# vacuumboard_eurobot2014_r1.net
KiCad netlist of a schematic drawn in EAGLE
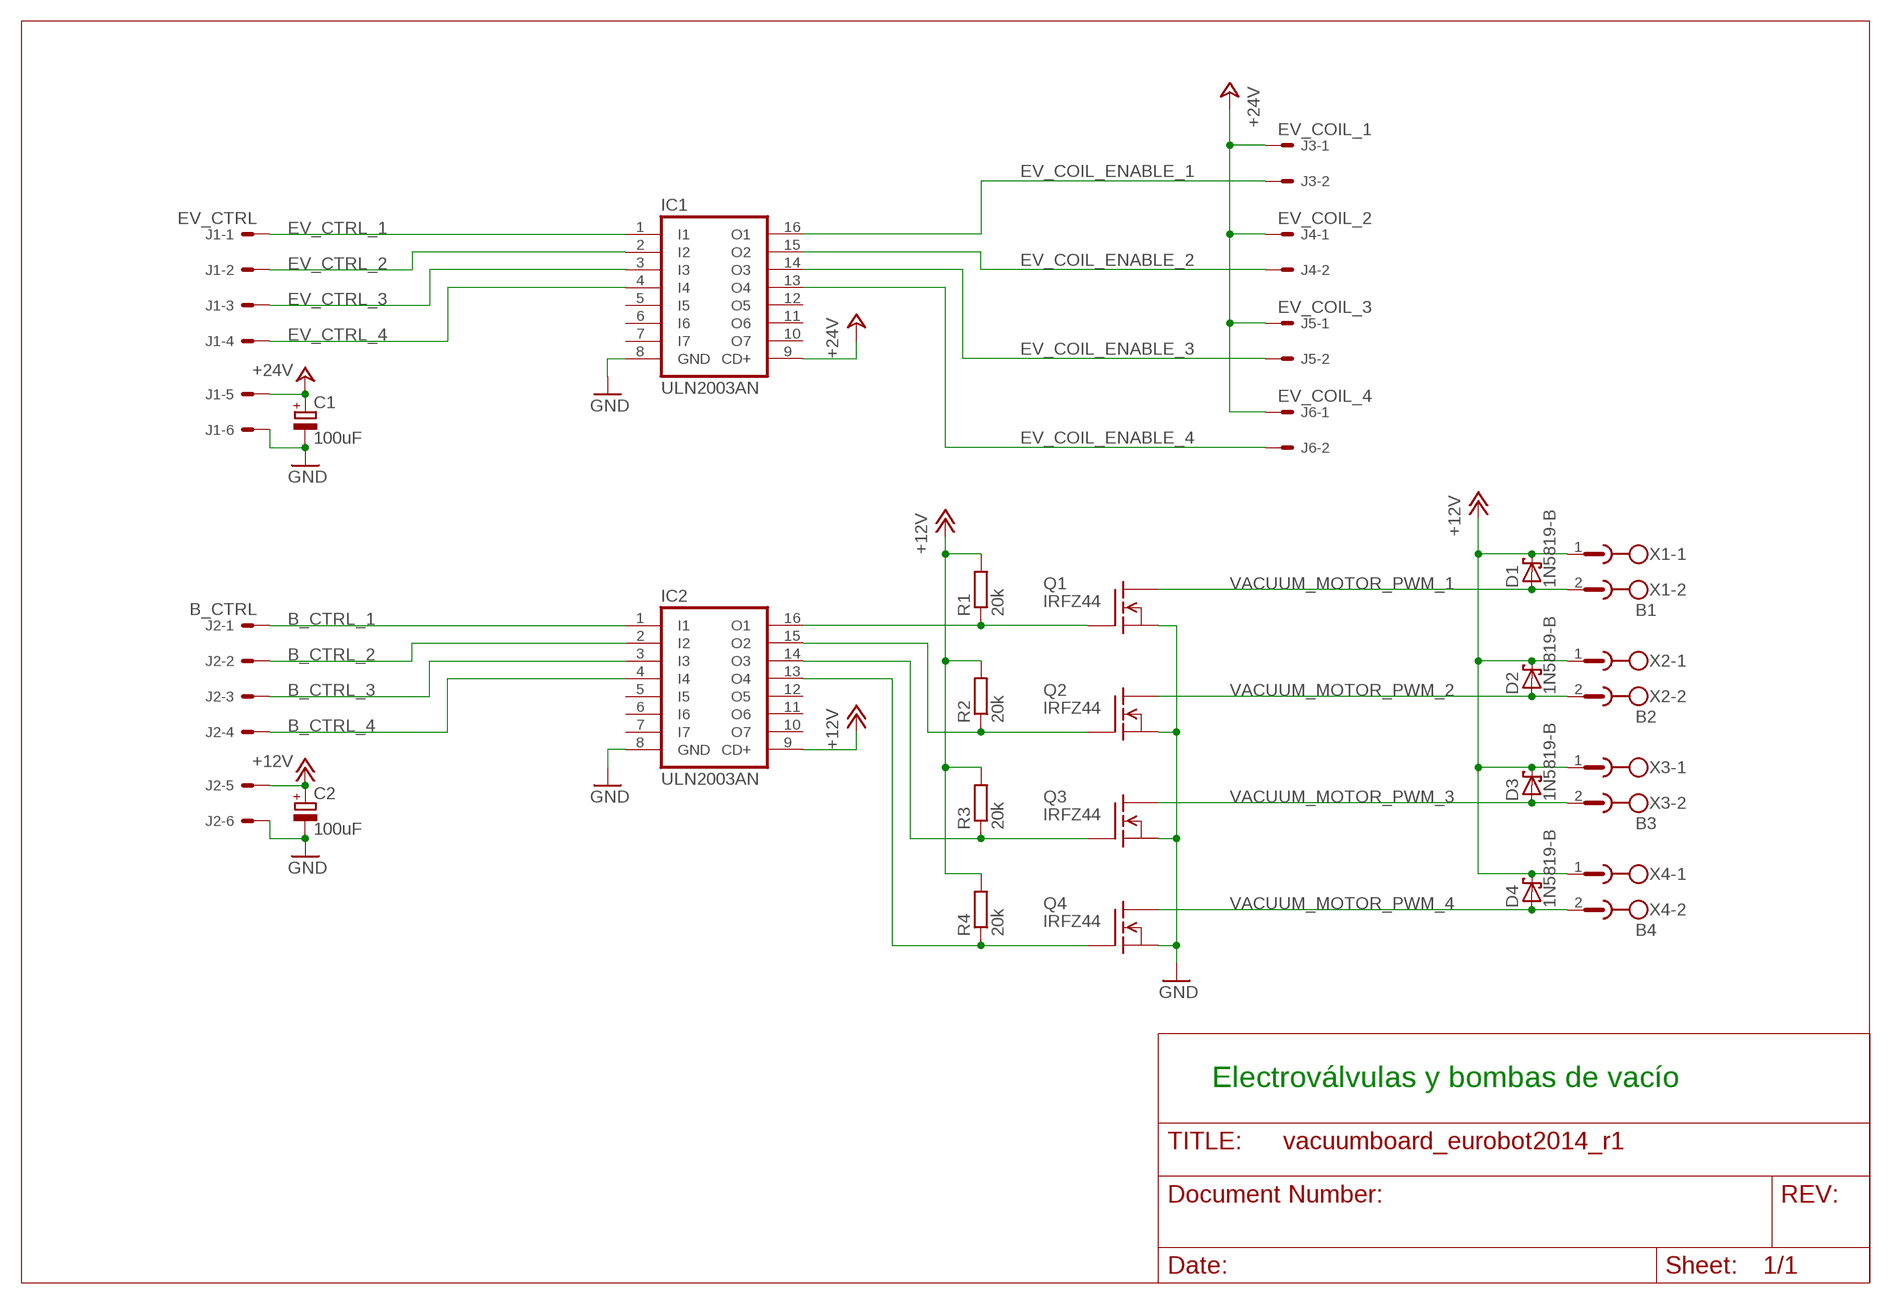
[diagram p0: schematic, sheet 1]

(export (version "E")
  (design (tool "Eeschema 10.0.6"))
  (components
    (comp (ref "C1")
      (value "100uF")
      (footprint "eagle-import:E3,5-8")
      (libsource (lib "eagle-import") (part "CPOL-EUE3.5-8"))
    )
    (comp (ref "C2")
      (value "100uF")
      (footprint "eagle-import:E3,5-8")
      (libsource (lib "eagle-import") (part "CPOL-EUE3.5-8"))
    )
    (comp (ref "D1")
      (value "1N5819-B")
      (footprint "eagle-import:DO41-7.6")
      (libsource (lib "eagle-import") (part "1N5819-B"))
    )
    (comp (ref "D2")
      (value "1N5819-B")
      (footprint "eagle-import:DO41-7.6")
      (libsource (lib "eagle-import") (part "1N5819-B"))
    )
    (comp (ref "D3")
      (value "1N5819-B")
      (footprint "eagle-import:DO41-7.6")
      (libsource (lib "eagle-import") (part "1N5819-B"))
    )
    (comp (ref "D4")
      (value "1N5819-B")
      (footprint "eagle-import:DO41-7.6")
      (libsource (lib "eagle-import") (part "1N5819-B"))
    )
    (comp (ref "IC1")
      (value "ULN2003AN")
      (footprint "eagle-import:DIL16")
      (libsource (lib "eagle-import") (part "ULN2003AN"))
    )
    (comp (ref "IC2")
      (value "ULN2003AN")
      (footprint "eagle-import:DIL16")
      (libsource (lib "eagle-import") (part "ULN2003AN"))
    )
    (comp (ref "J1")
      (value "EV_CTRL")
      (footprint "eagle-import:6410-06")
      (libsource (lib "eagle-import") (part "22-?-0627-2061"))
    )
    (comp (ref "J2")
      (value "B_CTRL")
      (footprint "eagle-import:6410-06")
      (fields (field (name "OC_FARNELL") "unknown") (field (name "OC_NEWARK") "unknown"))
      (libsource (lib "eagle-import") (part "22-?-0627-2061"))
    )
    (comp (ref "J3")
      (value "EV_COIL_1")
      (footprint "eagle-import:6410-02")
      (libsource (lib "eagle-import") (part "22-?-0227-2021"))
    )
    (comp (ref "J4")
      (value "EV_COIL_2")
      (footprint "eagle-import:6410-02")
      (libsource (lib "eagle-import") (part "22-?-0227-2021"))
    )
    (comp (ref "J5")
      (value "EV_COIL_3")
      (footprint "eagle-import:6410-02")
      (libsource (lib "eagle-import") (part "22-?-0227-2021"))
    )
    (comp (ref "J6")
      (value "EV_COIL_4")
      (footprint "eagle-import:6410-02")
      (libsource (lib "eagle-import") (part "22-?-0227-2021"))
    )
    (comp (ref "Q1")
      (value "IRFZ44")
      (footprint "eagle-import:TO220")
      (libsource (lib "eagle-import") (part "IRF510"))
    )
    (comp (ref "Q2")
      (value "IRFZ44")
      (footprint "eagle-import:TO220")
      (libsource (lib "eagle-import") (part "IRF510"))
    )
    (comp (ref "Q3")
      (value "IRFZ44")
      (footprint "eagle-import:TO220")
      (libsource (lib "eagle-import") (part "IRF510"))
    )
    (comp (ref "Q4")
      (value "IRFZ44")
      (footprint "eagle-import:TO220")
      (libsource (lib "eagle-import") (part "IRF510"))
    )
    (comp (ref "R1")
      (value "20k")
      (footprint "eagle-import:R0805")
      (libsource (lib "eagle-import") (part "R-EU_R0805"))
    )
    (comp (ref "R2")
      (value "20k")
      (footprint "eagle-import:R0805")
      (libsource (lib "eagle-import") (part "R-EU_R0805"))
    )
    (comp (ref "R3")
      (value "20k")
      (footprint "eagle-import:R0805")
      (libsource (lib "eagle-import") (part "R-EU_R0805"))
    )
    (comp (ref "R4")
      (value "20k")
      (footprint "eagle-import:R0805")
      (libsource (lib "eagle-import") (part "R-EU_R0805"))
    )
    (comp (ref "X1")
      (value "B1")
      (footprint "eagle-import:MSTBA2")
      (fields (field (name "MF") "FARNELL") (field (name "MPN") "1757242"))
      (libsource (lib "eagle-import") (part "MSTBA2"))
    )
    (comp (ref "X2")
      (value "B2")
      (footprint "eagle-import:MSTBA2")
      (fields (field (name "MF") "FARNELL") (field (name "MPN") "1757242"))
      (libsource (lib "eagle-import") (part "MSTBA2"))
    )
    (comp (ref "X3")
      (value "B3")
      (footprint "eagle-import:MSTBA2")
      (fields (field (name "MF") "FARNELL") (field (name "MPN") "1757242"))
      (libsource (lib "eagle-import") (part "MSTBA2"))
    )
    (comp (ref "X4")
      (value "B4")
      (footprint "eagle-import:MSTBA2")
      (fields (field (name "MF") "FARNELL") (field (name "MPN") "1757242"))
      (libsource (lib "eagle-import") (part "MSTBA2"))
    )
  )
  (nets
    (net (code "1") (name "+12V") (class "Default")
      (node (ref "C2") (pin "+") (pinfunction "+_+") (pintype "passive"))
      (node (ref "D1") (pin "C") (pinfunction "C_C") (pintype "passive"))
      (node (ref "D2") (pin "C") (pinfunction "C_C") (pintype "passive"))
      (node (ref "D3") (pin "C") (pinfunction "C_C") (pintype "passive"))
      (node (ref "D4") (pin "C") (pinfunction "C_C") (pintype "passive"))
      (node (ref "IC2") (pin "9") (pinfunction "CD+_9") (pintype "passive"))
      (node (ref "J2") (pin "5") (pinfunction "S_5") (pintype "passive"))
      (node (ref "R1") (pin "2") (pinfunction "2_2") (pintype "passive"))
      (node (ref "R2") (pin "2") (pinfunction "2_2") (pintype "passive"))
      (node (ref "R3") (pin "2") (pinfunction "2_2") (pintype "passive"))
      (node (ref "R4") (pin "2") (pinfunction "2_2") (pintype "passive"))
      (node (ref "X1") (pin "1") (pinfunction "1_1") (pintype "passive"))
      (node (ref "X2") (pin "1") (pinfunction "1_1") (pintype "passive"))
      (node (ref "X3") (pin "1") (pinfunction "1_1") (pintype "passive"))
      (node (ref "X4") (pin "1") (pinfunction "1_1") (pintype "passive"))
    )
    (net (code "2") (name "+24V") (class "Default")
      (node (ref "C1") (pin "+") (pinfunction "+_+") (pintype "passive"))
      (node (ref "IC1") (pin "9") (pinfunction "CD+_9") (pintype "passive"))
      (node (ref "J1") (pin "5") (pinfunction "S_5") (pintype "passive"))
      (node (ref "J3") (pin "1") (pinfunction "S_1") (pintype "passive"))
      (node (ref "J4") (pin "1") (pinfunction "S_1") (pintype "passive"))
      (node (ref "J5") (pin "1") (pinfunction "S_1") (pintype "passive"))
      (node (ref "J6") (pin "1") (pinfunction "S_1") (pintype "passive"))
    )
    (net (code "3") (name "/B_CTRL_1") (class "Default")
      (node (ref "IC2") (pin "1") (pinfunction "I1_1") (pintype "input"))
      (node (ref "J2") (pin "1") (pinfunction "S_1") (pintype "passive"))
    )
    (net (code "4") (name "/B_CTRL_2") (class "Default")
      (node (ref "IC2") (pin "2") (pinfunction "I2_2") (pintype "input"))
      (node (ref "J2") (pin "2") (pinfunction "S_2") (pintype "passive"))
    )
    (net (code "5") (name "/B_CTRL_3") (class "Default")
      (node (ref "IC2") (pin "3") (pinfunction "I3_3") (pintype "input"))
      (node (ref "J2") (pin "3") (pinfunction "S_3") (pintype "passive"))
    )
    (net (code "6") (name "/B_CTRL_4") (class "Default")
      (node (ref "IC2") (pin "4") (pinfunction "I4_4") (pintype "input"))
      (node (ref "J2") (pin "4") (pinfunction "S_4") (pintype "passive"))
    )
    (net (code "7") (name "/EV_COIL_ENABLE_1") (class "Default")
      (node (ref "IC1") (pin "16") (pinfunction "O1_16") (pintype "open_collector"))
      (node (ref "J3") (pin "2") (pinfunction "S_2") (pintype "passive"))
    )
    (net (code "8") (name "/EV_COIL_ENABLE_2") (class "Default")
      (node (ref "IC1") (pin "15") (pinfunction "O2_15") (pintype "open_collector"))
      (node (ref "J4") (pin "2") (pinfunction "S_2") (pintype "passive"))
    )
    (net (code "9") (name "/EV_COIL_ENABLE_3") (class "Default")
      (node (ref "IC1") (pin "14") (pinfunction "O3_14") (pintype "open_collector"))
      (node (ref "J5") (pin "2") (pinfunction "S_2") (pintype "passive"))
    )
    (net (code "10") (name "/EV_COIL_ENABLE_4") (class "Default")
      (node (ref "IC1") (pin "13") (pinfunction "O4_13") (pintype "open_collector"))
      (node (ref "J6") (pin "2") (pinfunction "S_2") (pintype "passive"))
    )
    (net (code "11") (name "/EV_CTRL_1") (class "Default")
      (node (ref "IC1") (pin "1") (pinfunction "I1_1") (pintype "input"))
      (node (ref "J1") (pin "1") (pinfunction "S_1") (pintype "passive"))
    )
    (net (code "12") (name "/EV_CTRL_2") (class "Default")
      (node (ref "IC1") (pin "2") (pinfunction "I2_2") (pintype "input"))
      (node (ref "J1") (pin "2") (pinfunction "S_2") (pintype "passive"))
    )
    (net (code "13") (name "/EV_CTRL_3") (class "Default")
      (node (ref "IC1") (pin "3") (pinfunction "I3_3") (pintype "input"))
      (node (ref "J1") (pin "3") (pinfunction "S_3") (pintype "passive"))
    )
    (net (code "14") (name "/EV_CTRL_4") (class "Default")
      (node (ref "IC1") (pin "4") (pinfunction "I4_4") (pintype "input"))
      (node (ref "J1") (pin "4") (pinfunction "S_4") (pintype "passive"))
    )
    (net (code "15") (name "/VACUUM_MOTOR_PWM_1") (class "Default")
      (node (ref "D1") (pin "A") (pinfunction "A_A") (pintype "passive"))
      (node (ref "Q1") (pin "2") (pinfunction "D_2") (pintype "passive"))
      (node (ref "X1") (pin "2") (pinfunction "1_2") (pintype "passive"))
    )
    (net (code "16") (name "/VACUUM_MOTOR_PWM_2") (class "Default")
      (node (ref "D2") (pin "A") (pinfunction "A_A") (pintype "passive"))
      (node (ref "Q2") (pin "2") (pinfunction "D_2") (pintype "passive"))
      (node (ref "X2") (pin "2") (pinfunction "1_2") (pintype "passive"))
    )
    (net (code "17") (name "/VACUUM_MOTOR_PWM_3") (class "Default")
      (node (ref "D3") (pin "A") (pinfunction "A_A") (pintype "passive"))
      (node (ref "Q3") (pin "2") (pinfunction "D_2") (pintype "passive"))
      (node (ref "X3") (pin "2") (pinfunction "1_2") (pintype "passive"))
    )
    (net (code "18") (name "/VACUUM_MOTOR_PWM_4") (class "Default")
      (node (ref "D4") (pin "A") (pinfunction "A_A") (pintype "passive"))
      (node (ref "Q4") (pin "2") (pinfunction "D_2") (pintype "passive"))
      (node (ref "X4") (pin "2") (pinfunction "1_2") (pintype "passive"))
    )
    (net (code "19") (name "GND") (class "Default")
      (node (ref "C1") (pin "-") (pinfunction "-_-") (pintype "passive"))
      (node (ref "C2") (pin "-") (pinfunction "-_-") (pintype "passive"))
      (node (ref "IC1") (pin "8") (pinfunction "GND_8") (pintype "power_in"))
      (node (ref "IC2") (pin "8") (pinfunction "GND_8") (pintype "power_in"))
      (node (ref "J1") (pin "6") (pinfunction "S_6") (pintype "passive"))
      (node (ref "J2") (pin "6") (pinfunction "S_6") (pintype "passive"))
      (node (ref "Q1") (pin "3") (pinfunction "S_3") (pintype "passive"))
      (node (ref "Q2") (pin "3") (pinfunction "S_3") (pintype "passive"))
      (node (ref "Q3") (pin "3") (pinfunction "S_3") (pintype "passive"))
      (node (ref "Q4") (pin "3") (pinfunction "S_3") (pintype "passive"))
    )
    (net (code "20") (name "Net-(IC2-O1)") (class "Default")
      (node (ref "IC2") (pin "16") (pinfunction "O1_16") (pintype "open_collector"))
      (node (ref "Q1") (pin "1") (pinfunction "G_1") (pintype "passive"))
      (node (ref "R1") (pin "1") (pinfunction "1_1") (pintype "passive"))
    )
    (net (code "21") (name "Net-(IC2-O2)") (class "Default")
      (node (ref "IC2") (pin "15") (pinfunction "O2_15") (pintype "open_collector"))
      (node (ref "Q2") (pin "1") (pinfunction "G_1") (pintype "passive"))
      (node (ref "R2") (pin "1") (pinfunction "1_1") (pintype "passive"))
    )
    (net (code "22") (name "Net-(IC2-O3)") (class "Default")
      (node (ref "IC2") (pin "14") (pinfunction "O3_14") (pintype "open_collector"))
      (node (ref "Q3") (pin "1") (pinfunction "G_1") (pintype "passive"))
      (node (ref "R3") (pin "1") (pinfunction "1_1") (pintype "passive"))
    )
    (net (code "23") (name "Net-(IC2-O4)") (class "Default")
      (node (ref "IC2") (pin "13") (pinfunction "O4_13") (pintype "open_collector"))
      (node (ref "Q4") (pin "1") (pinfunction "G_1") (pintype "passive"))
      (node (ref "R4") (pin "1") (pinfunction "1_1") (pintype "passive"))
    )
    (net (code "24") (name "unconnected-(IC1-I5-Pad5)") (class "Default")
      (node (ref "IC1") (pin "5") (pinfunction "I5_5") (pintype "input"))
    )
    (net (code "25") (name "unconnected-(IC1-I6-Pad6)") (class "Default")
      (node (ref "IC1") (pin "6") (pinfunction "I6_6") (pintype "input"))
    )
    (net (code "26") (name "unconnected-(IC1-I7-Pad7)") (class "Default")
      (node (ref "IC1") (pin "7") (pinfunction "I7_7") (pintype "input"))
    )
    (net (code "27") (name "unconnected-(IC1-O5-Pad12)") (class "Default")
      (node (ref "IC1") (pin "12") (pinfunction "O5_12") (pintype "open_collector"))
    )
    (net (code "28") (name "unconnected-(IC1-O6-Pad11)") (class "Default")
      (node (ref "IC1") (pin "11") (pinfunction "O6_11") (pintype "open_collector"))
    )
    (net (code "29") (name "unconnected-(IC1-O7-Pad10)") (class "Default")
      (node (ref "IC1") (pin "10") (pinfunction "O7_10") (pintype "open_collector"))
    )
    (net (code "30") (name "unconnected-(IC2-I5-Pad5)") (class "Default")
      (node (ref "IC2") (pin "5") (pinfunction "I5_5") (pintype "input"))
    )
    (net (code "31") (name "unconnected-(IC2-I6-Pad6)") (class "Default")
      (node (ref "IC2") (pin "6") (pinfunction "I6_6") (pintype "input"))
    )
    (net (code "32") (name "unconnected-(IC2-I7-Pad7)") (class "Default")
      (node (ref "IC2") (pin "7") (pinfunction "I7_7") (pintype "input"))
    )
    (net (code "33") (name "unconnected-(IC2-O5-Pad12)") (class "Default")
      (node (ref "IC2") (pin "12") (pinfunction "O5_12") (pintype "open_collector"))
    )
    (net (code "34") (name "unconnected-(IC2-O6-Pad11)") (class "Default")
      (node (ref "IC2") (pin "11") (pinfunction "O6_11") (pintype "open_collector"))
    )
    (net (code "35") (name "unconnected-(IC2-O7-Pad10)") (class "Default")
      (node (ref "IC2") (pin "10") (pinfunction "O7_10") (pintype "open_collector"))
    )
  )
)
